# M7347B.net
KiCad netlist of a schematic drawn in EAGLE
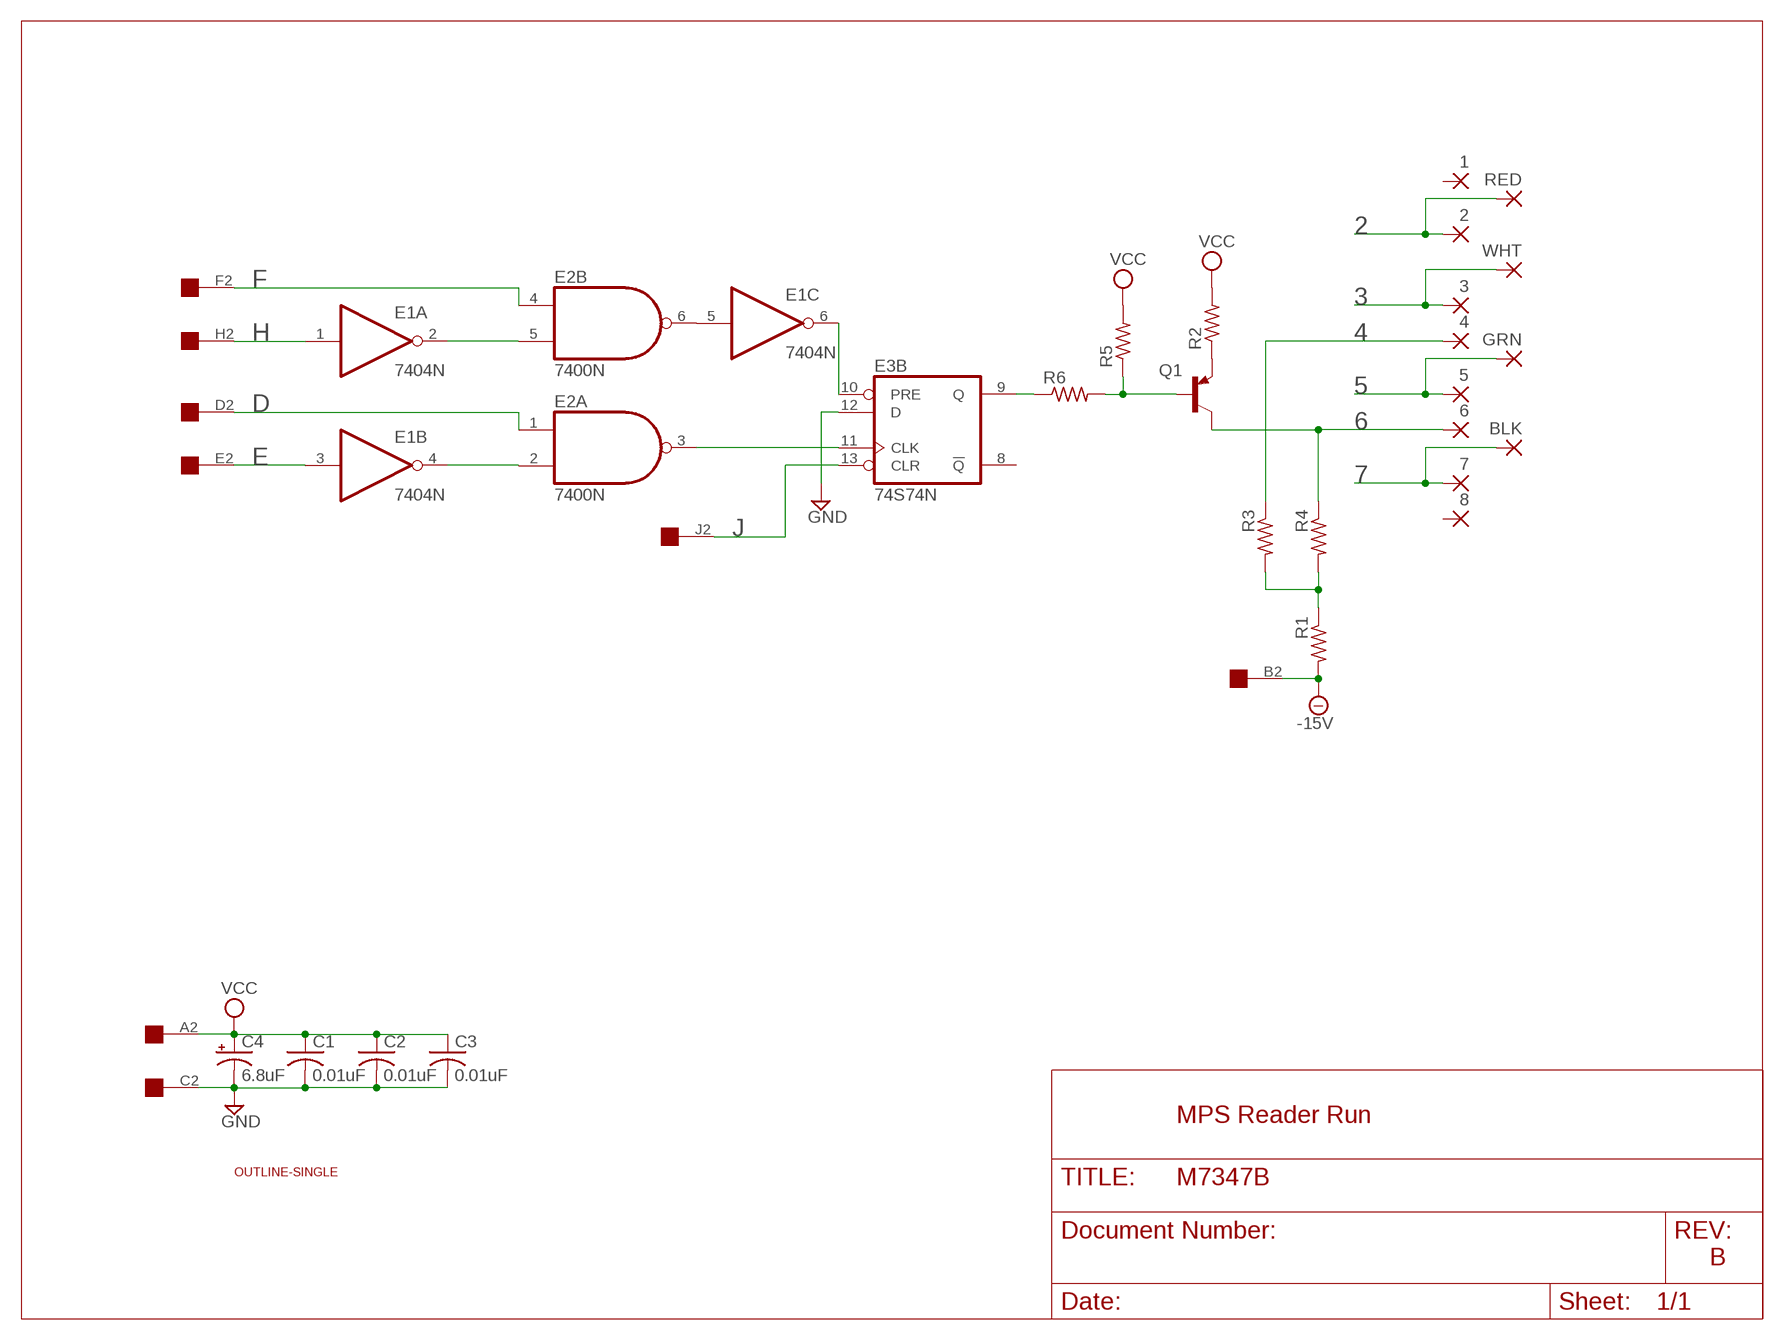
[diagram p0: schematic, sheet 1]

(export (version "E")
  (design (tool "Eeschema 10.0.6"))
  (components
    (comp (ref "1")
      (value "2,15/1,0")
      (footprint "eagle-import:2,15_1,0")
      (libsource (lib "eagle-import") (part "2,15/1,0"))
    )
    (comp (ref "2")
      (value "2,15/1,0")
      (footprint "eagle-import:2,15_1,0")
      (libsource (lib "eagle-import") (part "2,15/1,0"))
    )
    (comp (ref "3")
      (value "2,15/1,0")
      (footprint "eagle-import:2,15_1,0")
      (libsource (lib "eagle-import") (part "2,15/1,0"))
    )
    (comp (ref "4")
      (value "2,15/1,0")
      (footprint "eagle-import:2,15_1,0")
      (libsource (lib "eagle-import") (part "2,15/1,0"))
    )
    (comp (ref "5")
      (value "2,15/1,0")
      (footprint "eagle-import:2,15_1,0")
      (libsource (lib "eagle-import") (part "2,15/1,0"))
    )
    (comp (ref "6")
      (value "2,15/1,0")
      (footprint "eagle-import:2,15_1,0")
      (libsource (lib "eagle-import") (part "2,15/1,0"))
    )
    (comp (ref "7")
      (value "2,15/1,0")
      (footprint "eagle-import:2,15_1,0")
      (libsource (lib "eagle-import") (part "2,15/1,0"))
    )
    (comp (ref "8")
      (value "2,15/1,0")
      (footprint "eagle-import:2,15_1,0")
      (libsource (lib "eagle-import") (part "2,15/1,0"))
    )
    (comp (ref "BLK")
      (value "2,15/1,0")
      (footprint "eagle-import:2,15_1,0")
      (libsource (lib "eagle-import") (part "2,15/1,0"))
    )
    (comp (ref "C1")
      (value "0.01uF")
      (footprint "eagle-import:C050-025X075")
      (libsource (lib "eagle-import") (part "C-US050-025X075"))
    )
    (comp (ref "C2")
      (value "0.01uF")
      (footprint "eagle-import:C050-025X075")
      (libsource (lib "eagle-import") (part "C-US050-025X075"))
    )
    (comp (ref "C3")
      (value "0.01uF")
      (footprint "eagle-import:C050-025X075")
      (libsource (lib "eagle-import") (part "C-US050-025X075"))
    )
    (comp (ref "C4")
      (value "6.8uF")
      (footprint "eagle-import:E12-8")
      (libsource (lib "eagle-import") (part "CPOL-USE20-8AXIAL"))
    )
    (comp (ref "E1")
      (value "7404N")
      (footprint "eagle-import:DIL14")
      (libsource (lib "eagle-import") (part "7404N"))
    )
    (comp (ref "E2")
      (value "7400N")
      (footprint "eagle-import:DIL14")
      (libsource (lib "eagle-import") (part "7400N"))
    )
    (comp (ref "E3")
      (value "74S74N")
      (footprint "eagle-import:DIL14")
      (libsource (lib "eagle-import") (part "7474NS"))
    )
    (comp (ref "GRN")
      (value "2,15/1,0")
      (footprint "eagle-import:2,15_1,0")
      (libsource (lib "eagle-import") (part "2,15/1,0"))
    )
    (comp (ref "Q1")
      (value "-PNP-TO5")
      (footprint "eagle-import:TO5")
      (libsource (lib "eagle-import") (part "-PNP-TO5"))
    )
    (comp (ref "R1")
      (value "R-US_0207/10")
      (footprint "eagle-import:0207_10")
      (libsource (lib "eagle-import") (part "R-US_0207/10"))
    )
    (comp (ref "R2")
      (value "R-US_0207/10")
      (footprint "eagle-import:0207_10")
      (libsource (lib "eagle-import") (part "R-US_0207/10"))
    )
    (comp (ref "R3")
      (value "R-US_0207/10")
      (footprint "eagle-import:0207_10")
      (libsource (lib "eagle-import") (part "R-US_0207/10"))
    )
    (comp (ref "R4")
      (value "R-US_0207/10")
      (footprint "eagle-import:0207_10")
      (libsource (lib "eagle-import") (part "R-US_0207/10"))
    )
    (comp (ref "R5")
      (value "R-US_0207/10")
      (footprint "eagle-import:0207_10")
      (libsource (lib "eagle-import") (part "R-US_0207/10"))
    )
    (comp (ref "R6")
      (value "R-US_0207/10")
      (footprint "eagle-import:0207_10")
      (libsource (lib "eagle-import") (part "R-US_0207/10"))
    )
    (comp (ref "RED")
      (value "2,15/1,0")
      (footprint "eagle-import:2,15_1,0")
      (libsource (lib "eagle-import") (part "2,15/1,0"))
    )
    (comp (ref "U$1")
      (value "EDGE-1")
      (footprint "eagle-import:EDGE-CON1")
      (libsource (lib "eagle-import") (part "EDGE-1"))
    )
    (comp (ref "U$2")
      (value "OUTLINE-SINGLE")
      (footprint "eagle-import:SINGLE")
      (libsource (lib "eagle-import") (part "OUTLINE-SINGLE"))
    )
    (comp (ref "WHT")
      (value "2,15/1,0")
      (footprint "eagle-import:2,15_1,0")
      (libsource (lib "eagle-import") (part "2,15/1,0"))
    )
  )
  (nets
    (net (code "1") (name "-15V") (class "Default")
      (node (ref "R1") (pin "2") (pinfunction "2_2") (pintype "passive"))
      (node (ref "U$1") (pin "B2") (pinfunction "1_B2") (pintype "bidirectional"))
    )
    (net (code "2") (name "/2") (class "Default")
      (node (ref "2") (pin "1") (pinfunction "P_1") (pintype "passive"))
      (node (ref "RED") (pin "1") (pinfunction "P_1") (pintype "passive"))
    )
    (net (code "3") (name "/3") (class "Default")
      (node (ref "3") (pin "1") (pinfunction "P_1") (pintype "passive"))
      (node (ref "WHT") (pin "1") (pinfunction "P_1") (pintype "passive"))
    )
    (net (code "4") (name "/4") (class "Default")
      (node (ref "4") (pin "1") (pinfunction "P_1") (pintype "passive"))
      (node (ref "R3") (pin "1") (pinfunction "1_1") (pintype "passive"))
    )
    (net (code "5") (name "/5") (class "Default")
      (node (ref "5") (pin "1") (pinfunction "P_1") (pintype "passive"))
      (node (ref "GRN") (pin "1") (pinfunction "P_1") (pintype "passive"))
    )
    (net (code "6") (name "/6") (class "Default")
      (node (ref "6") (pin "1") (pinfunction "P_1") (pintype "passive"))
      (node (ref "Q1") (pin "3") (pinfunction "C_3") (pintype "passive"))
      (node (ref "R4") (pin "1") (pinfunction "1_1") (pintype "passive"))
    )
    (net (code "7") (name "/7") (class "Default")
      (node (ref "7") (pin "1") (pinfunction "P_1") (pintype "passive"))
      (node (ref "BLK") (pin "1") (pinfunction "P_1") (pintype "passive"))
    )
    (net (code "8") (name "/D") (class "Default")
      (node (ref "E2") (pin "1") (pinfunction "I0_1") (pintype "input"))
      (node (ref "U$1") (pin "D2") (pinfunction "1_D2") (pintype "bidirectional"))
    )
    (net (code "9") (name "/E") (class "Default")
      (node (ref "E1") (pin "3") (pinfunction "I_3") (pintype "input"))
      (node (ref "U$1") (pin "E2") (pinfunction "1_E2") (pintype "bidirectional"))
    )
    (net (code "10") (name "/F") (class "Default")
      (node (ref "E2") (pin "4") (pinfunction "I0_4") (pintype "input"))
      (node (ref "U$1") (pin "F2") (pinfunction "1_F2") (pintype "bidirectional"))
    )
    (net (code "11") (name "/H") (class "Default")
      (node (ref "E1") (pin "1") (pinfunction "I_1") (pintype "input"))
      (node (ref "U$1") (pin "H2") (pinfunction "1_H2") (pintype "bidirectional"))
    )
    (net (code "12") (name "/J") (class "Default")
      (node (ref "E3") (pin "13") (pinfunction "CLR_13") (pintype "input"))
      (node (ref "U$1") (pin "J2") (pinfunction "1_J2") (pintype "bidirectional"))
    )
    (net (code "13") (name "GND") (class "Default")
      (node (ref "C1") (pin "2") (pinfunction "2_2") (pintype "passive"))
      (node (ref "C2") (pin "2") (pinfunction "2_2") (pintype "passive"))
      (node (ref "C3") (pin "2") (pinfunction "2_2") (pintype "passive"))
      (node (ref "C4") (pin "-") (pinfunction "-_-") (pintype "passive"))
      (node (ref "E3") (pin "12") (pinfunction "D_12") (pintype "input"))
      (node (ref "U$1") (pin "C2") (pinfunction "1_C2") (pintype "bidirectional"))
    )
    (net (code "14") (name "Net-(E1A-O)") (class "Default")
      (node (ref "E1") (pin "2") (pinfunction "O_2") (pintype "output"))
      (node (ref "E2") (pin "5") (pinfunction "I1_5") (pintype "input"))
    )
    (net (code "15") (name "Net-(E1B-O)") (class "Default")
      (node (ref "E1") (pin "4") (pinfunction "O_4") (pintype "output"))
      (node (ref "E2") (pin "2") (pinfunction "I1_2") (pintype "input"))
    )
    (net (code "16") (name "Net-(E1C-I)") (class "Default")
      (node (ref "E1") (pin "5") (pinfunction "I_5") (pintype "input"))
      (node (ref "E2") (pin "6") (pinfunction "O_6") (pintype "output"))
    )
    (net (code "17") (name "Net-(E1C-O)") (class "Default")
      (node (ref "E1") (pin "6") (pinfunction "O_6") (pintype "output"))
      (node (ref "E3") (pin "10") (pinfunction "PRE_10") (pintype "input"))
    )
    (net (code "18") (name "Net-(E2A-O)") (class "Default")
      (node (ref "E2") (pin "3") (pinfunction "O_3") (pintype "output"))
      (node (ref "E3") (pin "11") (pinfunction "CLK_11") (pintype "input"))
    )
    (net (code "19") (name "Net-(E3B-Q)") (class "Default")
      (node (ref "E3") (pin "9") (pinfunction "Q_9") (pintype "output"))
      (node (ref "R6") (pin "1") (pinfunction "1_1") (pintype "passive"))
    )
    (net (code "20") (name "Net-(Q1-B)") (class "Default")
      (node (ref "Q1") (pin "2") (pinfunction "B_2") (pintype "passive"))
      (node (ref "R5") (pin "1") (pinfunction "1_1") (pintype "passive"))
      (node (ref "R6") (pin "2") (pinfunction "2_2") (pintype "passive"))
    )
    (net (code "21") (name "Net-(Q1-E)") (class "Default")
      (node (ref "Q1") (pin "1") (pinfunction "E_1") (pintype "passive"))
      (node (ref "R2") (pin "1") (pinfunction "1_1") (pintype "passive"))
    )
    (net (code "22") (name "Net-(R1-Pad1)") (class "Default")
      (node (ref "R1") (pin "1") (pinfunction "1_1") (pintype "passive"))
      (node (ref "R3") (pin "2") (pinfunction "2_2") (pintype "passive"))
      (node (ref "R4") (pin "2") (pinfunction "2_2") (pintype "passive"))
    )
    (net (code "23") (name "VCC") (class "Default")
      (node (ref "C1") (pin "1") (pinfunction "1_1") (pintype "passive"))
      (node (ref "C2") (pin "1") (pinfunction "1_1") (pintype "passive"))
      (node (ref "C3") (pin "1") (pinfunction "1_1") (pintype "passive"))
      (node (ref "C4") (pin "+") (pinfunction "+_+") (pintype "passive"))
      (node (ref "R2") (pin "2") (pinfunction "2_2") (pintype "passive"))
      (node (ref "R5") (pin "2") (pinfunction "2_2") (pintype "passive"))
      (node (ref "U$1") (pin "A2") (pinfunction "1_A2") (pintype "bidirectional"))
    )
    (net (code "24") (name "unconnected-(1-P-Pad1)") (class "Default")
      (node (ref "1") (pin "1") (pinfunction "P_1") (pintype "passive"))
    )
    (net (code "25") (name "unconnected-(8-P-Pad1)") (class "Default")
      (node (ref "8") (pin "1") (pinfunction "P_1") (pintype "passive"))
    )
    (net (code "26") (name "unconnected-(E3B-~{Q}-Pad8)") (class "Default")
      (node (ref "E3") (pin "8") (pinfunction "~{Q}_8") (pintype "output"))
    )
  )
)
